# Photocoupler12Vinput.net
KiCad netlist of a schematic drawn in Altium Designer
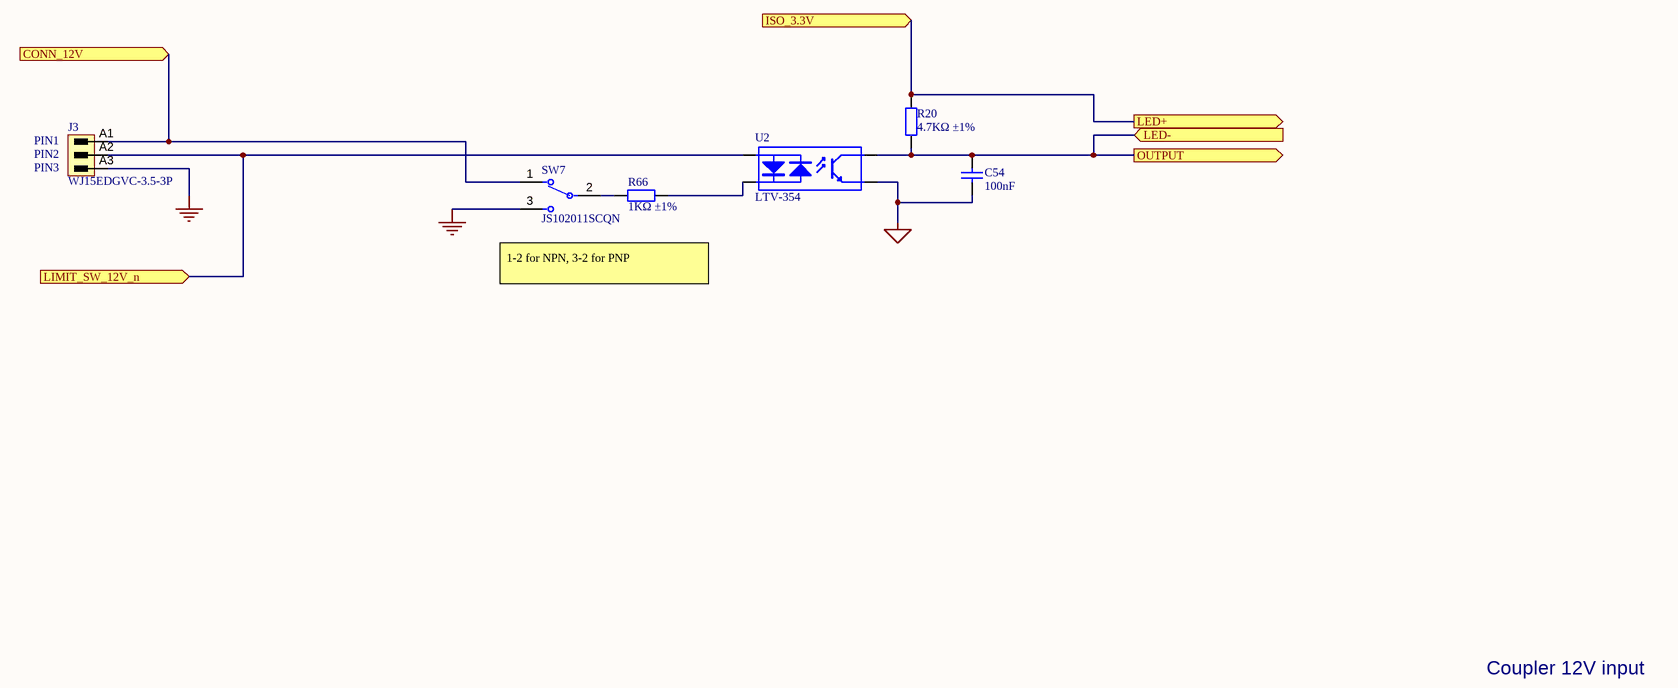
[diagram p0: Photocoupler12Vinput.SchDoc]

(export (version "E")
  (design (tool "Eeschema 10.0.6"))
  (components
    (comp (ref "C54")
      (value "100nF")
      (footprint "0402_C")
      (description "Chip capacitors")
      (fields
        (field (name "MANUFACTURER") "Samsung Electro-Mechanics")
        (field (name "PARTNUMBER") "CL05B104KO5NNNC")
      )
      (libsource (lib "Cap") (part "0402 100nF (104) 10% 16V"))
    )
    (comp (ref "J3")
      (value "WJ15EDGVC-3.5-3P")
      (footprint "691321100003 - 3.5mm  3p")
      (fields (field (name "MANUFACTURER") "Ningbo Kangnex Elec"))
      (libsource (lib "Universal_CNC_Breakout") (part "3.5mm Terminal Header 3p"))
    )
    (comp (ref "R20")
      (value "4.7KΩ ±1%")
      (footprint "0402_R")
      (description "Chip resistor")
      (fields (field (name "MANUFACTURER") "Uniroyal Elec") (field (name "PARTNUMBER") "0402WGF4701TCE"))
      (libsource (lib "RES") (part "0402 4.7K (4701) 1%"))
    )
    (comp (ref "R66")
      (value "1KΩ ±1%")
      (footprint "0402_R")
      (description "Chip resistor")
      (fields (field (name "MANUFACTURER") "Uniroyal Elec") (field (name "PARTNUMBER") "0402WGF1001TCE"))
      (libsource (lib "RES") (part "0402 1K (1001) 1%"))
    )
    (comp (ref "SW7")
      (value "JS102011SCQN")
      (footprint "FP-JS102011SCQN-MFG")
      (description "Switch Slide SPDT Top Slide 0.3A 30VDC Gull Wing SMD T/R")
      (libsource (lib "Cambridge Mobile Telematics, Inc") (part "39e195cbbadc85d1df0d7eb6847d379"))
    )
    (comp (ref "U2")
      (value "LTV-354")
      (footprint "Miscellaneous Devices LC:SOP-4_P2.54")
      (libsource (lib "IC") (part "LTV-354"))
    )
  )
  (nets
    (net (code "1") (name "/CONN_12V") (class "Default")
      (node (ref "J3") (pin "A1") (pinfunction "A1_A1") (pintype "passive"))
      (node (ref "SW7") (pin "1") (pinfunction "1_1") (pintype "passive"))
    )
    (net (code "2") (name "/ISO_3.3V") (class "Default")
      (node (ref "R20") (pin "2") (pinfunction "2_2") (pintype "passive"))
    )
    (net (code "3") (name "/LED-") (class "Default")
      (node (ref "C54") (pin "2") (pinfunction "2_2") (pintype "passive"))
      (node (ref "R20") (pin "1") (pinfunction "1_1") (pintype "passive"))
      (node (ref "U2") (pin "4") (pinfunction "C_4") (pintype "passive"))
    )
    (net (code "4") (name "/LIMIT_SW_12V_n") (class "Default")
      (node (ref "J3") (pin "A2") (pinfunction "A2_A2") (pintype "passive"))
      (node (ref "U2") (pin "1") (pinfunction "A_1") (pintype "passive"))
    )
    (net (code "5") (name "GND") (class "Default")
      (node (ref "J3") (pin "A3") (pinfunction "A3_A3") (pintype "passive"))
      (node (ref "SW7") (pin "3") (pinfunction "3_3") (pintype "passive"))
    )
    (net (code "6") (name "MCU_GND") (class "Default")
      (node (ref "C54") (pin "1") (pinfunction "1_1") (pintype "passive"))
      (node (ref "U2") (pin "3") (pinfunction "E_3") (pintype "passive"))
    )
    (net (code "7") (name "Net-(SW7-C)") (class "Default")
      (node (ref "R66") (pin "2") (pinfunction "2_2") (pintype "passive"))
      (node (ref "SW7") (pin "2") (pinfunction "C_2") (pintype "passive"))
    )
    (net (code "8") (name "Net-(U2-K)") (class "Default")
      (node (ref "R66") (pin "1") (pinfunction "1_1") (pintype "passive"))
      (node (ref "U2") (pin "2") (pinfunction "K_2") (pintype "passive"))
    )
  )
)
